# wdc.net
KiCad netlist of a schematic drawn in EAGLE
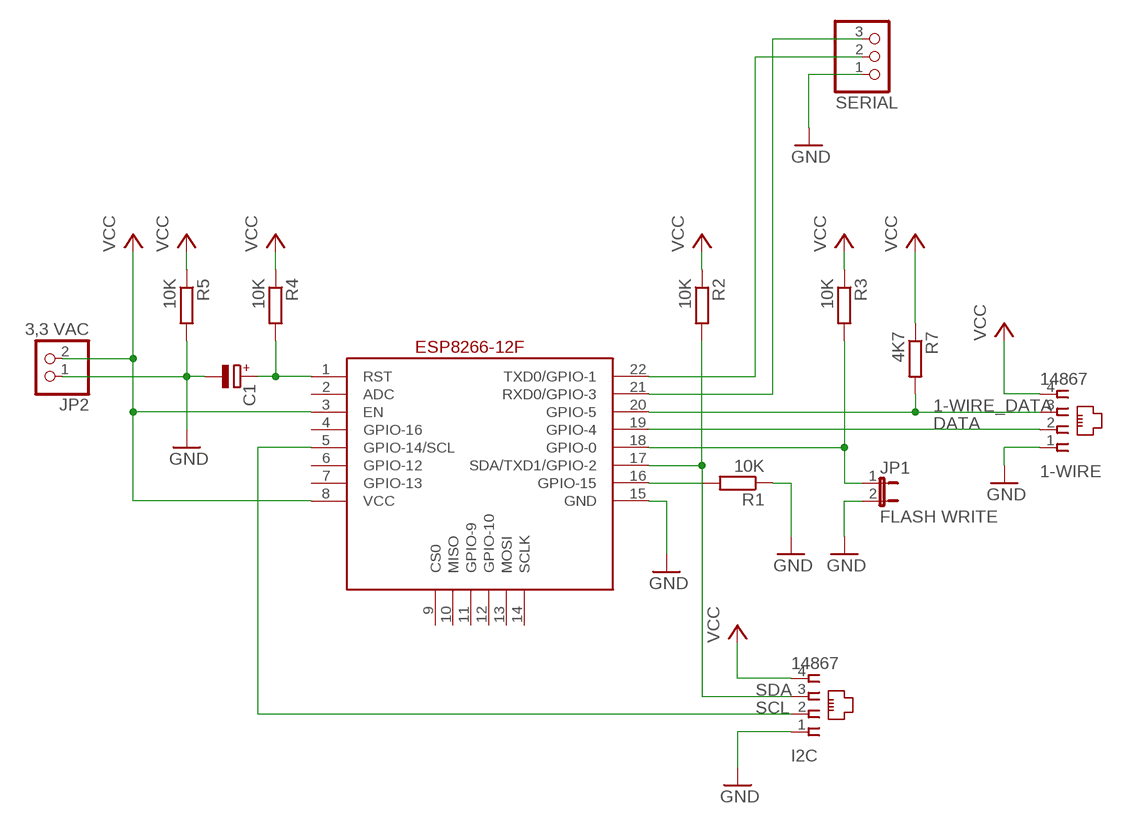
[diagram p0: schematic, sheet 1]

(export (version "E")
  (design (tool "Eeschema 10.0.6"))
  (components
    (comp (ref "1-WIRE")
      (value "14867")
      (footprint "eagle-import:14867")
      (libsource (lib "eagle-import") (part "14867"))
    )
    (comp (ref "C1")
      (value "CPOL-EUE2-5")
      (footprint "eagle-import:E2-5")
      (libsource (lib "eagle-import") (part "CPOL-EUE2-5"))
    )
    (comp (ref "I2C")
      (value "14867")
      (footprint "eagle-import:14867")
      (libsource (lib "eagle-import") (part "14867"))
    )
    (comp (ref "JP1")
      (value "FLASH WRITE")
      (footprint "eagle-import:JP1")
      (libsource (lib "eagle-import") (part "JP1E"))
    )
    (comp (ref "JP2")
      (value "3,3 VAC")
      (footprint "eagle-import:1X02")
      (libsource (lib "eagle-import") (part "PINHD-1X2"))
    )
    (comp (ref "R1")
      (value "10K")
      (footprint "eagle-import:0204_7")
      (libsource (lib "eagle-import") (part "R-EU_0204/7"))
    )
    (comp (ref "R2")
      (value "10K")
      (footprint "eagle-import:0204_7")
      (libsource (lib "eagle-import") (part "R-EU_0204/7"))
    )
    (comp (ref "R3")
      (value "10K")
      (footprint "eagle-import:0204_7")
      (libsource (lib "eagle-import") (part "R-EU_0204/7"))
    )
    (comp (ref "R4")
      (value "10K")
      (footprint "eagle-import:0204_7")
      (libsource (lib "eagle-import") (part "R-EU_0204/7"))
    )
    (comp (ref "R5")
      (value "10K")
      (footprint "eagle-import:0204_7")
      (libsource (lib "eagle-import") (part "R-EU_0204/7"))
    )
    (comp (ref "R7")
      (value "4K7")
      (footprint "eagle-import:0204_7")
      (libsource (lib "eagle-import") (part "R-EU_0204/7"))
    )
    (comp (ref "SERIAL")
      (value "PINHD-1X3")
      (footprint "eagle-import:1X03")
      (libsource (lib "eagle-import") (part "PINHD-1X3"))
    )
    (comp (ref "U$1")
      (value "ESP826612F")
      (footprint "eagle-import:ESP826612F")
      (libsource (lib "eagle-import") (part "ESP826612F"))
    )
  )
  (nets
    (net (code "1") (name "/1-WIRE_DATA") (class "Default")
      (node (ref "1-WIRE") (pin "3") (pinfunction "3_3") (pintype "passive"))
      (node (ref "R7") (pin "2") (pinfunction "2_2") (pintype "passive"))
      (node (ref "U$1") (pin "20") (pinfunction "GPIO-5_20") (pintype "bidirectional"))
    )
    (net (code "2") (name "/DATA") (class "Default")
      (node (ref "1-WIRE") (pin "2") (pinfunction "2_2") (pintype "passive"))
      (node (ref "U$1") (pin "19") (pinfunction "GPIO-4_19") (pintype "bidirectional"))
    )
    (net (code "3") (name "/SCL") (class "Default")
      (node (ref "I2C") (pin "2") (pinfunction "2_2") (pintype "passive"))
      (node (ref "U$1") (pin "5") (pinfunction "GPIO-14/SCL_5") (pintype "bidirectional"))
    )
    (net (code "4") (name "/SDA") (class "Default")
      (node (ref "I2C") (pin "3") (pinfunction "3_3") (pintype "passive"))
      (node (ref "R2") (pin "2") (pinfunction "2_2") (pintype "passive"))
      (node (ref "U$1") (pin "17") (pinfunction "SDA/TXD1/GPIO-2_17") (pintype "bidirectional"))
    )
    (net (code "5") (name "GND") (class "Default")
      (node (ref "1-WIRE") (pin "1") (pinfunction "1_1") (pintype "passive"))
      (node (ref "C1") (pin "-") (pinfunction "-_-") (pintype "passive"))
      (node (ref "I2C") (pin "1") (pinfunction "1_1") (pintype "passive"))
      (node (ref "JP1") (pin "2") (pinfunction "2_2") (pintype "passive"))
      (node (ref "JP2") (pin "1") (pinfunction "1_1") (pintype "passive"))
      (node (ref "R1") (pin "1") (pinfunction "1_1") (pintype "passive"))
      (node (ref "R5") (pin "2") (pinfunction "2_2") (pintype "passive"))
      (node (ref "SERIAL") (pin "1") (pinfunction "1_1") (pintype "passive"))
      (node (ref "U$1") (pin "15") (pinfunction "GND_15") (pintype "bidirectional"))
    )
    (net (code "6") (name "Net-(U$1-GPIO-0)") (class "Default")
      (node (ref "JP1") (pin "1") (pinfunction "1_1") (pintype "passive"))
      (node (ref "R3") (pin "2") (pinfunction "2_2") (pintype "passive"))
      (node (ref "U$1") (pin "18") (pinfunction "GPIO-0_18") (pintype "bidirectional"))
    )
    (net (code "7") (name "Net-(U$1-GPIO-15)") (class "Default")
      (node (ref "R1") (pin "2") (pinfunction "2_2") (pintype "passive"))
      (node (ref "U$1") (pin "16") (pinfunction "GPIO-15_16") (pintype "bidirectional"))
    )
    (net (code "8") (name "Net-(U$1-RST)") (class "Default")
      (node (ref "C1") (pin "+") (pinfunction "+_+") (pintype "passive"))
      (node (ref "R4") (pin "2") (pinfunction "2_2") (pintype "passive"))
      (node (ref "U$1") (pin "1") (pinfunction "RST_1") (pintype "bidirectional"))
    )
    (net (code "9") (name "Net-(U$1-RXD0{slash}GPIO-3)") (class "Default")
      (node (ref "SERIAL") (pin "3") (pinfunction "3_3") (pintype "passive"))
      (node (ref "U$1") (pin "21") (pinfunction "RXD0/GPIO-3_21") (pintype "bidirectional"))
    )
    (net (code "10") (name "Net-(U$1-TXD0{slash}GPIO-1)") (class "Default")
      (node (ref "SERIAL") (pin "2") (pinfunction "2_2") (pintype "passive"))
      (node (ref "U$1") (pin "22") (pinfunction "TXD0/GPIO-1_22") (pintype "bidirectional"))
    )
    (net (code "11") (name "VCC") (class "Default")
      (node (ref "1-WIRE") (pin "4") (pinfunction "4_4") (pintype "passive"))
      (node (ref "I2C") (pin "4") (pinfunction "4_4") (pintype "passive"))
      (node (ref "JP2") (pin "2") (pinfunction "2_2") (pintype "passive"))
      (node (ref "R2") (pin "1") (pinfunction "1_1") (pintype "passive"))
      (node (ref "R3") (pin "1") (pinfunction "1_1") (pintype "passive"))
      (node (ref "R4") (pin "1") (pinfunction "1_1") (pintype "passive"))
      (node (ref "R5") (pin "1") (pinfunction "1_1") (pintype "passive"))
      (node (ref "R7") (pin "1") (pinfunction "1_1") (pintype "passive"))
      (node (ref "U$1") (pin "3") (pinfunction "EN_3") (pintype "bidirectional"))
      (node (ref "U$1") (pin "8") (pinfunction "VCC_8") (pintype "bidirectional"))
    )
    (net (code "12") (name "unconnected-(U$1-ADC-Pad2)") (class "Default")
      (node (ref "U$1") (pin "2") (pinfunction "ADC_2") (pintype "bidirectional"))
    )
    (net (code "13") (name "unconnected-(U$1-CS0-Pad9)") (class "Default")
      (node (ref "U$1") (pin "9") (pinfunction "CS0_9") (pintype "bidirectional"))
    )
    (net (code "14") (name "unconnected-(U$1-GPIO-9-Pad11)") (class "Default")
      (node (ref "U$1") (pin "11") (pinfunction "GPIO-9_11") (pintype "bidirectional"))
    )
    (net (code "15") (name "unconnected-(U$1-GPIO-10-Pad12)") (class "Default")
      (node (ref "U$1") (pin "12") (pinfunction "GPIO-10_12") (pintype "bidirectional"))
    )
    (net (code "16") (name "unconnected-(U$1-GPIO-12-Pad6)") (class "Default")
      (node (ref "U$1") (pin "6") (pinfunction "GPIO-12_6") (pintype "bidirectional"))
    )
    (net (code "17") (name "unconnected-(U$1-GPIO-13-Pad7)") (class "Default")
      (node (ref "U$1") (pin "7") (pinfunction "GPIO-13_7") (pintype "bidirectional"))
    )
    (net (code "18") (name "unconnected-(U$1-GPIO-16-Pad4)") (class "Default")
      (node (ref "U$1") (pin "4") (pinfunction "GPIO-16_4") (pintype "bidirectional"))
    )
    (net (code "19") (name "unconnected-(U$1-MISO-Pad10)") (class "Default")
      (node (ref "U$1") (pin "10") (pinfunction "MISO_10") (pintype "bidirectional"))
    )
    (net (code "20") (name "unconnected-(U$1-MOSI-Pad13)") (class "Default")
      (node (ref "U$1") (pin "13") (pinfunction "MOSI_13") (pintype "bidirectional"))
    )
    (net (code "21") (name "unconnected-(U$1-SCLK-Pad14)") (class "Default")
      (node (ref "U$1") (pin "14") (pinfunction "SCLK_14") (pintype "bidirectional"))
    )
  )
)
